# 3V3_LDO_Regulator.net
KiCad netlist of a schematic drawn in Altium Designer
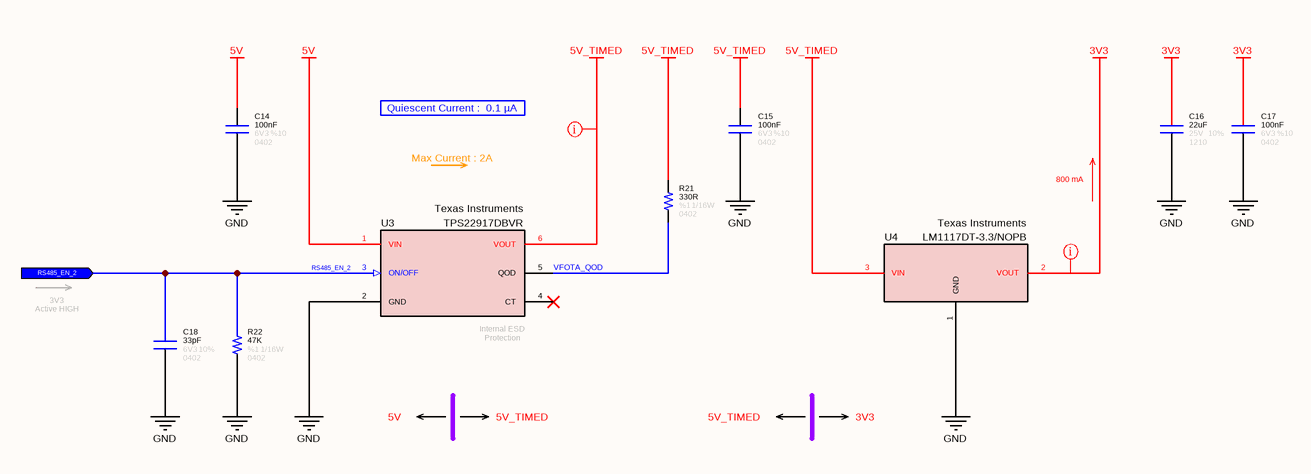
[diagram p0: 3V3 LDO Regulator.SchDoc]

(export (version "E")
  (design (tool "Eeschema 10.0.6"))
  (components
    (comp (ref "C14")
      (value "100nF")
      (footprint "CAPACITOR_0402")
      (description "Capacitor - 100nF [0402-6V3] (Ceramic)")
      (fields
        (field (name "MANUFACTURER PART NUMBER") "04026D104KAT4A")
        (field (name "TOLERANCE") "%10")
        (field (name "VOLTAGE") "6V3")
        (field (name "CASE") "0402")
        (field (name "Comment") "Capacitor - 100nF [0402] (Ceramic)")
      )
      (libsource (lib "Akkoyun") (part "Capacitor - 100nF [0402-6V3]"))
    )
    (comp (ref "C15")
      (value "100nF")
      (footprint "CAPACITOR_0402")
      (description "Capacitor - 100nF [0402-6V3] (Ceramic)")
      (fields
        (field (name "MANUFACTURER PART NUMBER") "04026D104KAT4A")
        (field (name "TOLERANCE") "%10")
        (field (name "VOLTAGE") "6V3")
        (field (name "CASE") "0402")
        (field (name "Comment") "Capacitor - 100nF [0402] (Ceramic)")
      )
      (libsource (lib "Akkoyun") (part "Capacitor - 100nF [0402-6V3]"))
    )
    (comp (ref "C16")
      (value "22uF")
      (footprint "CAPACITOR_0603")
      (description "Multilayer Ceramic Capacitors MLCC - SMD/SMT 22UF 25V 10% 1210")
      (fields
        (field (name "MANUFACTURER PART NUMBER") "GRM32ER71E226KE15L")
        (field (name "TOLERANCE") "10%")
        (field (name "CASE") "1210")
        (field (name "VOLTAGE") "25V")
        (field (name "Comment") "Capacitor - 22uF [1210] (Ceramic)")
      )
      (libsource (lib "Akkoyun") (part "Capacitor - 22uF [1210-6V3]"))
    )
    (comp (ref "C17")
      (value "100nF")
      (footprint "CAPACITOR_0402")
      (description "Capacitor - 100nF [0402-6V3] (Ceramic)")
      (fields
        (field (name "MANUFACTURER PART NUMBER") "04026D104KAT4A")
        (field (name "TOLERANCE") "%10")
        (field (name "VOLTAGE") "6V3")
        (field (name "CASE") "0402")
        (field (name "Comment") "Capacitor - 100nF [0402] (Ceramic)")
      )
      (libsource (lib "Akkoyun") (part "Capacitor - 100nF [0402-6V3]"))
    )
    (comp (ref "C18")
      (value "33pF")
      (footprint "CAPACITOR_0402")
      (description "Capacitor - 33pF [0402] (Ceramic)")
      (fields
        (field (name "MANUFACTURER PART NUMBER") "C0402C330J9RACAUTO")
        (field (name "TOLERANCE") "10%")
        (field (name "CASE") "0402")
        (field (name "VOLTAGE") "6V3")
      )
      (libsource (lib "Akkoyun") (part "Capacitor - 33pF [0402-6V3]"))
    )
    (comp (ref "R21")
      (value "330R")
      (footprint "RESISTOR_0402")
      (description "Thick Film Resistors - SMD 1/16 W 330 Ohm 1%")
      (fields
        (field (name "MANUFACTURER PART NUMBER") "CRCW0402330RFKED")
        (field (name "CASE") "0402")
        (field (name "TOLERANCE") "%1")
        (field (name "POWER") "1/16W")
        (field (name "Comment") "330R - 0402 - %1 - 1/16W")
      )
      (libsource (lib "Akkoyun") (part "Resistor - 330R [0402]"))
    )
    (comp (ref "R22")
      (value "47K")
      (footprint "RESISTOR_0402")
      (description "Thick Film Resistors - SMD 1/16 W 47 KOhm 1%")
      (fields
        (field (name "MANUFACTURER PART NUMBER") "CRCW040247K0FKED")
        (field (name "TOLERANCE") "%1")
        (field (name "CASE") "0402")
        (field (name "POWER") "1/16W")
        (field (name "Comment") "47K - 0402 - %1 - 1/16W")
      )
      (libsource (lib "Akkoyun") (part "Resistor - 47K [0402]"))
    )
    (comp (ref "U3")
      (value "Power Switch")
      (footprint "SOT-23-6")
      (description "Power Switch MosFet")
      (fields
        (field (name "MANUFACTURER PART NUMBER") "TPS22917DBVR")
        (field (name "MANUFACTURER NAME") "Texas Instruments")
      )
      (libsource (lib "Akkoyun") (part "IC - TPS22917"))
    )
    (comp (ref "U4")
      (value "LDO Regulator")
      (footprint "TO-252")
      (description "LDO Voltage Regulators 800MA LDO LINEAR REG")
      (fields
        (field (name "MANUFACTURER PART NUMBER") "LM1117DT-3.3/NOPB")
        (field (name "MANUFACTURER NAME") "Texas Instruments")
      )
      (libsource (lib "Akkoyun") (part "IC - LM1117DT-3.3/NOPB"))
    )
  )
  (nets
    (net (code "1") (name "/RS485_EN_2") (class "Default")
      (node (ref "C18") (pin "2") (pinfunction "2_2") (pintype "passive"))
      (node (ref "R22") (pin "2") (pinfunction "2_2") (pintype "passive"))
      (node (ref "U3") (pin "3") (pinfunction "ON/OFF_3") (pintype "input"))
    )
    (net (code "2") (name "/VFOTA_QOD") (class "Default")
      (node (ref "R21") (pin "1") (pinfunction "1_1") (pintype "passive"))
      (node (ref "U3") (pin "5") (pinfunction "QOD_5") (pintype "power_in"))
    )
    (net (code "3") (name "3V3") (class "Default")
      (node (ref "C16") (pin "2") (pinfunction "2_2") (pintype "passive"))
      (node (ref "C17") (pin "2") (pinfunction "2_2") (pintype "passive"))
      (node (ref "U4") (pin "2") (pinfunction "VOUT_2") (pintype "power_in"))
    )
    (net (code "4") (name "5V") (class "Default")
      (node (ref "C14") (pin "2") (pinfunction "2_2") (pintype "passive"))
      (node (ref "U3") (pin "1") (pinfunction "VIN_1") (pintype "power_in"))
    )
    (net (code "5") (name "5V_TIMED") (class "Default")
      (node (ref "C15") (pin "2") (pinfunction "2_2") (pintype "passive"))
      (node (ref "R21") (pin "2") (pinfunction "2_2") (pintype "passive"))
      (node (ref "U3") (pin "6") (pinfunction "VOUT_6") (pintype "power_in"))
      (node (ref "U4") (pin "3") (pinfunction "VIN_3") (pintype "power_in"))
    )
    (net (code "6") (name "GND") (class "Default")
      (node (ref "C14") (pin "1") (pinfunction "1_1") (pintype "passive"))
      (node (ref "C15") (pin "1") (pinfunction "1_1") (pintype "passive"))
      (node (ref "C16") (pin "1") (pinfunction "1_1") (pintype "passive"))
      (node (ref "C17") (pin "1") (pinfunction "1_1") (pintype "passive"))
      (node (ref "C18") (pin "1") (pinfunction "1_1") (pintype "passive"))
      (node (ref "R22") (pin "1") (pinfunction "1_1") (pintype "passive"))
      (node (ref "U3") (pin "2") (pinfunction "GND_2") (pintype "power_in"))
      (node (ref "U4") (pin "1") (pinfunction "GND_1") (pintype "power_in"))
    )
    (net (code "7") (name "unconnected-(U3-CT-Pad4)") (class "Default")
      (node (ref "U3") (pin "4") (pinfunction "CT_4") (pintype "power_in+no_connect"))
    )
  )
)
